# Sensor.net
KiCad netlist of a schematic drawn in EasyEDA
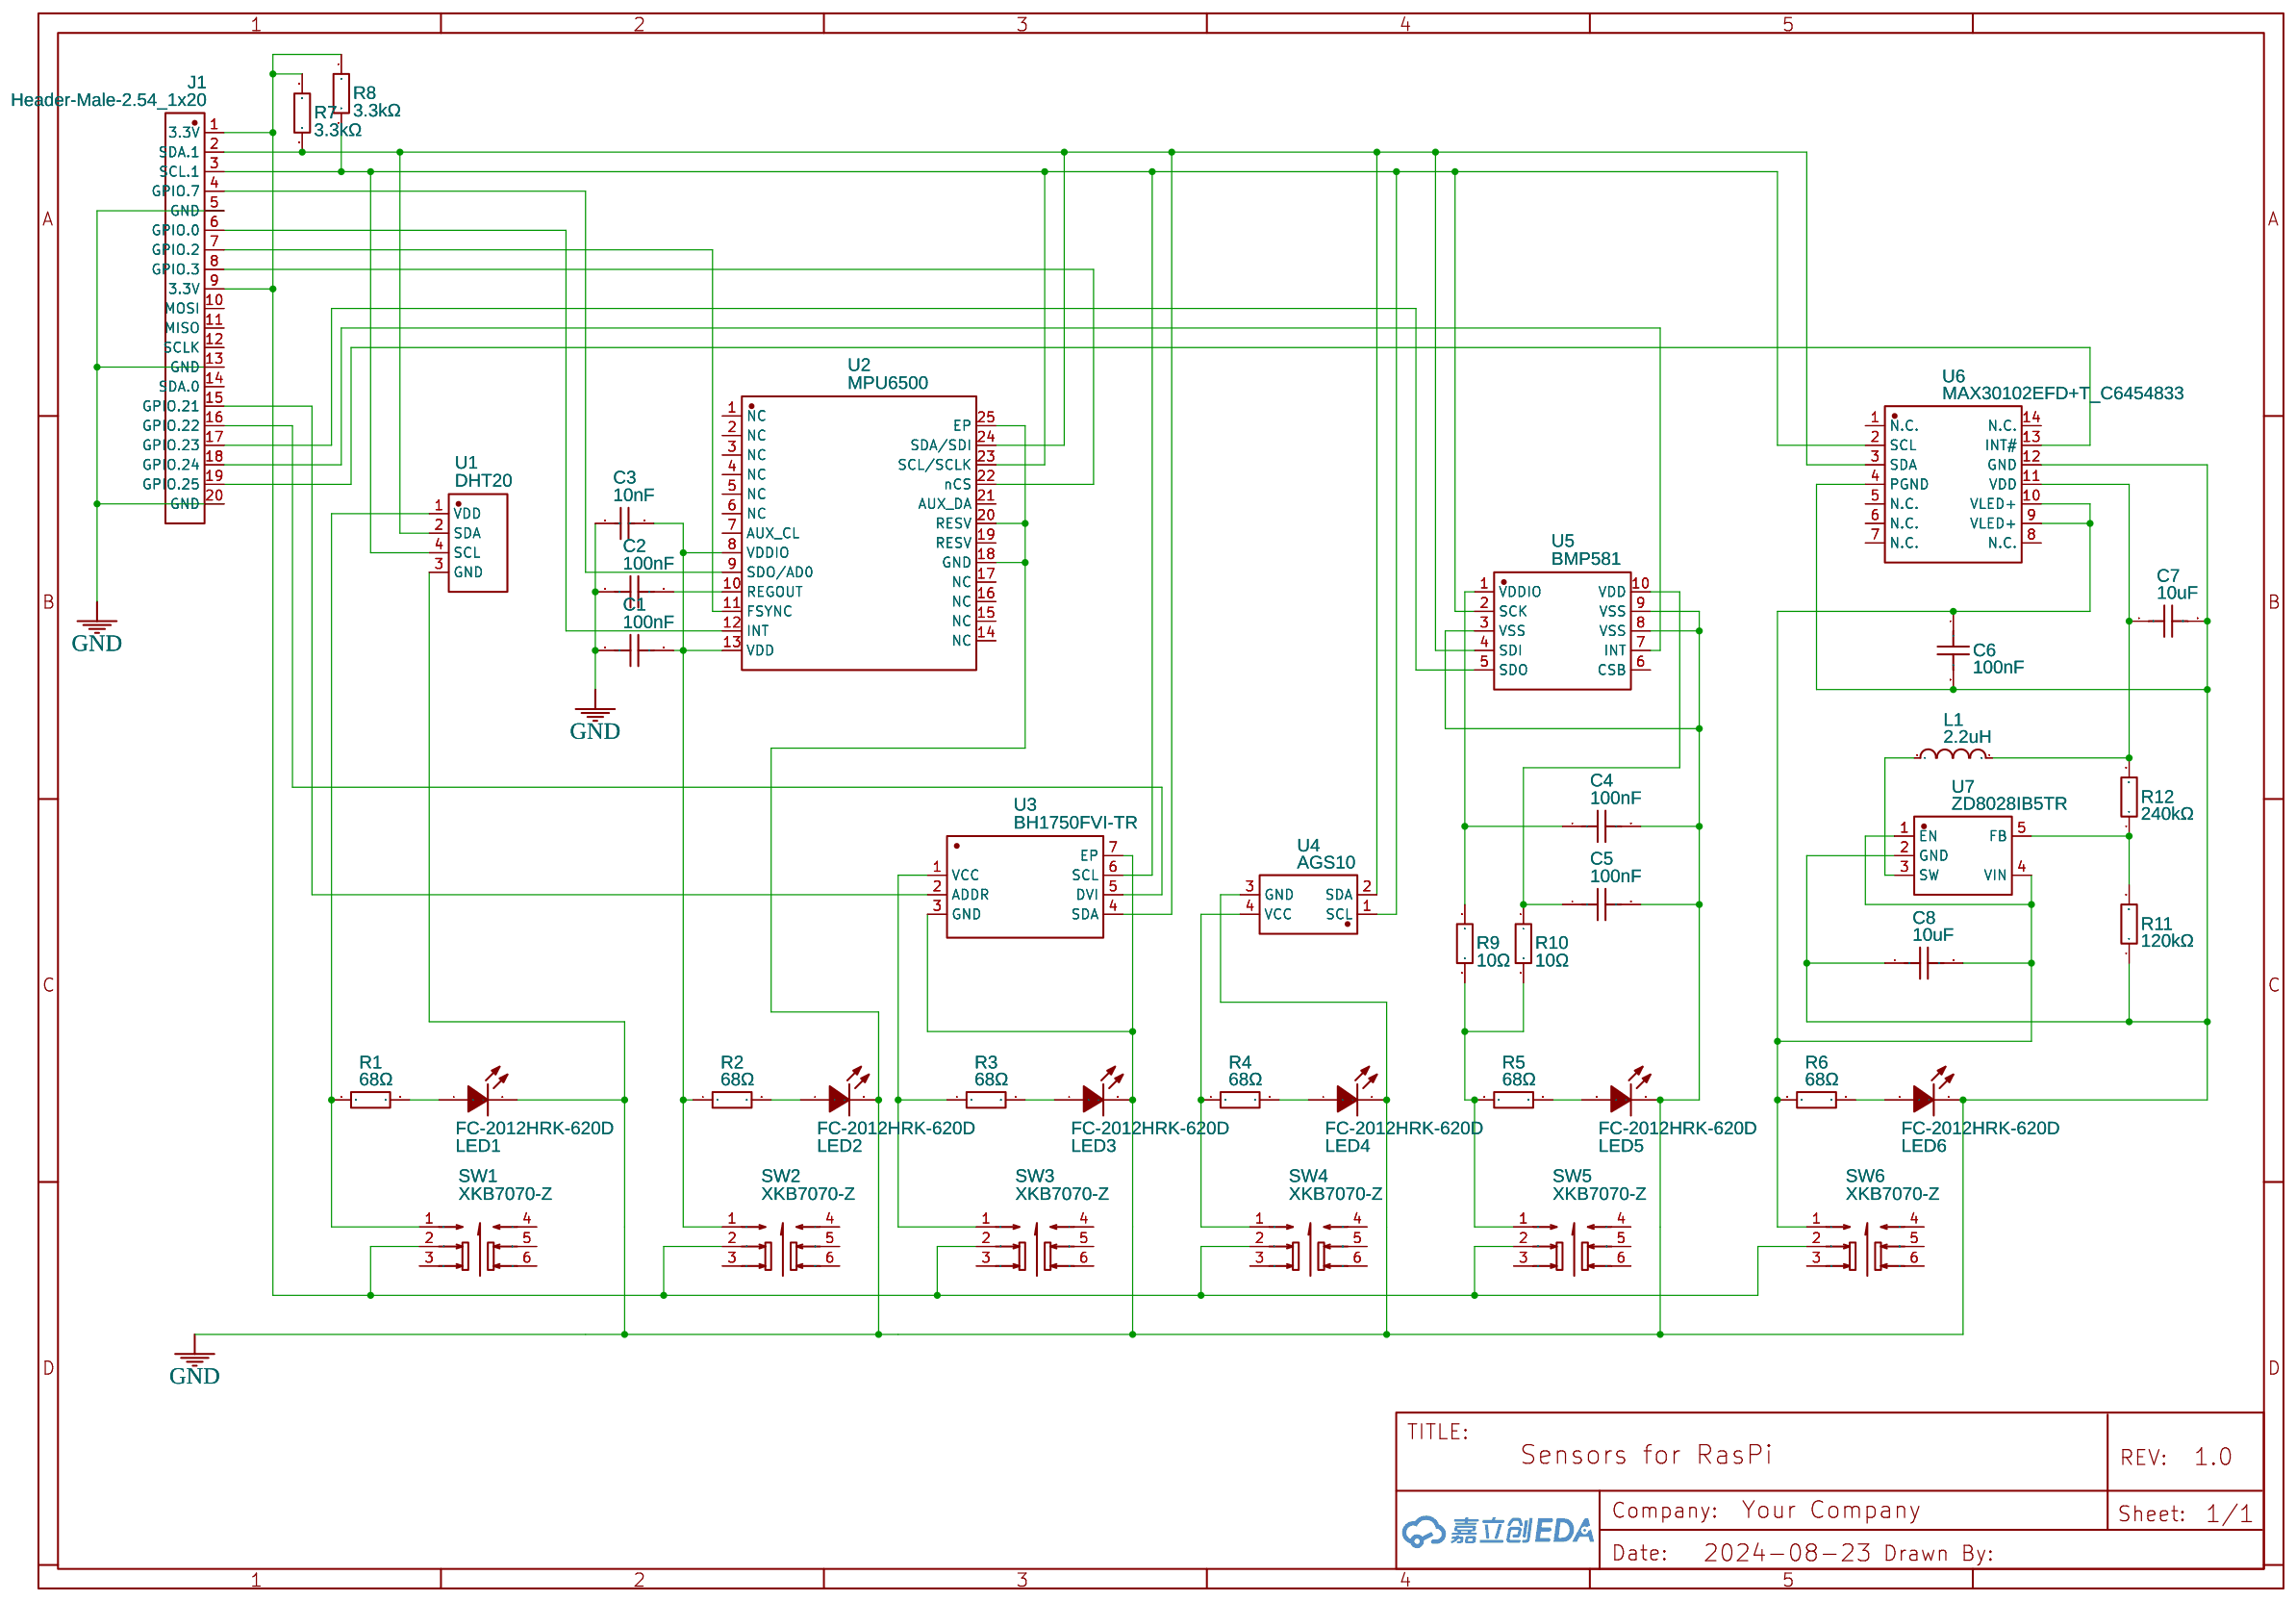
[diagram p0: schematic sheet]

(export (version "E")
  (design (tool "Eeschema 10.0.6"))
  (components
    (comp (ref "C1")
      (value "100nF")
      (fields
        (field (name "Manufacturer Part") "CC0603KRX7R9BB104")
        (field (name "Manufacturer") "YAGEO(国巨)")
      )
      (libsource (lib "") (part "CC0603KRX7R9BB104"))
    )
    (comp (ref "C2")
      (value "100nF")
      (fields
        (field (name "Manufacturer Part") "CC0603KRX7R9BB104")
        (field (name "Manufacturer") "YAGEO(国巨)")
      )
      (libsource (lib "") (part "CC0603KRX7R9BB104"))
    )
    (comp (ref "C3")
      (value "10nF")
      (fields
        (field (name "Manufacturer Part") "CC0603KRX7R9BB103")
        (field (name "Manufacturer") "YAGEO(国巨)")
      )
      (libsource (lib "") (part "CC0603KRX7R9BB103"))
    )
    (comp (ref "C4")
      (value "100nF")
      (fields
        (field (name "Manufacturer Part") "CC0603KRX7R9BB104")
        (field (name "Manufacturer") "YAGEO(国巨)")
      )
      (libsource (lib "") (part "CC0603KRX7R9BB104"))
    )
    (comp (ref "C5")
      (value "100nF")
      (fields
        (field (name "Manufacturer Part") "CC0603KRX7R9BB104")
        (field (name "Manufacturer") "YAGEO(国巨)")
      )
      (libsource (lib "") (part "CC0603KRX7R9BB104"))
    )
    (comp (ref "C6")
      (value "100nF")
      (fields
        (field (name "Manufacturer Part") "CC0603KRX7R9BB104")
        (field (name "Manufacturer") "YAGEO(国巨)")
      )
      (libsource (lib "") (part "CC0603KRX7R9BB104_1"))
    )
    (comp (ref "C7")
      (value "10uF")
      (fields
        (field (name "Manufacturer Part") "CL21A106KAYNNNE")
        (field (name "Manufacturer") "SAMSUNG(三星)")
      )
      (libsource (lib "") (part "CL21A106KAYNNNE"))
    )
    (comp (ref "C8")
      (value "10uF")
      (fields
        (field (name "Manufacturer Part") "CL21A106KAYNNNE")
        (field (name "Manufacturer") "SAMSUNG(三星)")
      )
      (libsource (lib "") (part "CL21A106KAYNNNE"))
    )
    (comp (ref "J1")
      (value "Header-Male-2.54_1x20")
      (fields (field (name "Manufacturer Part") "2.54-1*20P直针") (field (name "Manufacturer") "BOOMELE(博穆精密)"))
      (libsource (lib "") (part "Header-Male-2.54_1x20"))
    )
    (comp (ref "L1")
      (value "2.2uH")
      (fields (field (name "Manufacturer Part") "CMI201209U2R2KT") (field (name "Manufacturer") "FH(风华)"))
      (libsource (lib "") (part "CMI201209U2R2KT"))
    )
    (comp (ref "LED1")
      (value "FC-2012HRK-620D")
      (fields (field (name "Manufacturer Part") "NCD0805R1") (field (name "Manufacturer") "国星光电"))
      (libsource (lib "") (part "FC-2012HRK-620D"))
    )
    (comp (ref "LED2")
      (value "FC-2012HRK-620D")
      (fields (field (name "Manufacturer Part") "NCD0805R1") (field (name "Manufacturer") "国星光电"))
      (libsource (lib "") (part "FC-2012HRK-620D"))
    )
    (comp (ref "LED3")
      (value "FC-2012HRK-620D")
      (fields (field (name "Manufacturer Part") "NCD0805R1") (field (name "Manufacturer") "国星光电"))
      (libsource (lib "") (part "FC-2012HRK-620D"))
    )
    (comp (ref "LED4")
      (value "FC-2012HRK-620D")
      (fields (field (name "Manufacturer Part") "NCD0805R1") (field (name "Manufacturer") "国星光电"))
      (libsource (lib "") (part "FC-2012HRK-620D"))
    )
    (comp (ref "LED5")
      (value "FC-2012HRK-620D")
      (fields (field (name "Manufacturer Part") "NCD0805R1") (field (name "Manufacturer") "国星光电"))
      (libsource (lib "") (part "FC-2012HRK-620D"))
    )
    (comp (ref "LED6")
      (value "FC-2012HRK-620D")
      (fields (field (name "Manufacturer Part") "NCD0805R1") (field (name "Manufacturer") "国星光电"))
      (libsource (lib "") (part "FC-2012HRK-620D"))
    )
    (comp (ref "R1")
      (value "68Ω")
      (fields
        (field (name "Manufacturer Part") "0805W8F680JT5E")
        (field (name "Manufacturer") "UNI-ROYAL(厚声)")
      )
      (libsource (lib "") (part "0805W8F680JT5E"))
    )
    (comp (ref "R2")
      (value "68Ω")
      (fields
        (field (name "Manufacturer Part") "0805W8F680JT5E")
        (field (name "Manufacturer") "UNI-ROYAL(厚声)")
      )
      (libsource (lib "") (part "0805W8F680JT5E"))
    )
    (comp (ref "R3")
      (value "68Ω")
      (fields
        (field (name "Manufacturer Part") "0805W8F680JT5E")
        (field (name "Manufacturer") "UNI-ROYAL(厚声)")
      )
      (libsource (lib "") (part "0805W8F680JT5E"))
    )
    (comp (ref "R4")
      (value "68Ω")
      (fields
        (field (name "Manufacturer Part") "0805W8F680JT5E")
        (field (name "Manufacturer") "UNI-ROYAL(厚声)")
      )
      (libsource (lib "") (part "0805W8F680JT5E"))
    )
    (comp (ref "R5")
      (value "68Ω")
      (fields
        (field (name "Manufacturer Part") "0805W8F680JT5E")
        (field (name "Manufacturer") "UNI-ROYAL(厚声)")
      )
      (libsource (lib "") (part "0805W8F680JT5E"))
    )
    (comp (ref "R6")
      (value "68Ω")
      (fields
        (field (name "Manufacturer Part") "0805W8F680JT5E")
        (field (name "Manufacturer") "UNI-ROYAL(厚声)")
      )
      (libsource (lib "") (part "0805W8F680JT5E"))
    )
    (comp (ref "R7")
      (value "3.3kΩ")
      (fields
        (field (name "Manufacturer Part") "0603WAF3301T5E")
        (field (name "Manufacturer") "UNI-ROYAL(厚声)")
      )
      (libsource (lib "") (part "0603WAF3301T5E_1"))
    )
    (comp (ref "R8")
      (value "3.3kΩ")
      (fields
        (field (name "Manufacturer Part") "0603WAF3301T5E")
        (field (name "Manufacturer") "UNI-ROYAL(厚声)")
      )
      (libsource (lib "") (part "0603WAF3301T5E"))
    )
    (comp (ref "R9")
      (value "10Ω")
      (fields
        (field (name "Manufacturer Part") "0603WAF100JT5E")
        (field (name "Manufacturer") "UNI-ROYAL(厚声)")
      )
      (libsource (lib "") (part "0603WAF100JT5E_1"))
    )
    (comp (ref "R10")
      (value "10Ω")
      (fields
        (field (name "Manufacturer Part") "0603WAF100JT5E")
        (field (name "Manufacturer") "UNI-ROYAL(厚声)")
      )
      (libsource (lib "") (part "0603WAF100JT5E"))
    )
    (comp (ref "R11")
      (value "120kΩ")
      (fields
        (field (name "Manufacturer Part") "0603WAF1203T5E")
        (field (name "Manufacturer") "UNI-ROYAL(厚声)")
      )
      (libsource (lib "") (part "0603WAF1203T5E"))
    )
    (comp (ref "R12")
      (value "240kΩ")
      (fields
        (field (name "Manufacturer Part") "0603WAF2403T5E")
        (field (name "Manufacturer") "UNI-ROYAL(厚声)")
      )
      (libsource (lib "") (part "0603WAF2403T5E"))
    )
    (comp (ref "SW1")
      (value "XKB7070-Z")
      (fields (field (name "Manufacturer") "XKB Connectivity(中国星坤)"))
      (libsource (lib "") (part "XKB7070-Z"))
    )
    (comp (ref "SW2")
      (value "XKB7070-Z")
      (fields (field (name "Manufacturer") "XKB Connectivity(中国星坤)"))
      (libsource (lib "") (part "XKB7070-Z"))
    )
    (comp (ref "SW3")
      (value "XKB7070-Z")
      (fields (field (name "Manufacturer") "XKB Connectivity(中国星坤)"))
      (libsource (lib "") (part "XKB7070-Z"))
    )
    (comp (ref "SW4")
      (value "XKB7070-Z")
      (fields (field (name "Manufacturer") "XKB Connectivity(中国星坤)"))
      (libsource (lib "") (part "XKB7070-Z"))
    )
    (comp (ref "SW5")
      (value "XKB7070-Z")
      (fields (field (name "Manufacturer") "XKB Connectivity(中国星坤)"))
      (libsource (lib "") (part "XKB7070-Z"))
    )
    (comp (ref "SW6")
      (value "XKB7070-Z")
      (fields (field (name "Manufacturer") "XKB Connectivity(中国星坤)"))
      (libsource (lib "") (part "XKB7070-Z"))
    )
    (comp (ref "U1")
      (value "DHT20")
      (fields (field (name "Manufacturer") "广州奥松"))
      (libsource (lib "") (part "DHT20"))
    )
    (comp (ref "U2")
      (value "MPU6500")
      (fields
        (field (name "Manufacturer Part") "MPU-6500")
        (field (name "Manufacturer") "TDK InvenSense(应美盛)")
      )
      (libsource (lib "") (part "MPU6500"))
    )
    (comp (ref "U3")
      (value "BH1750FVI-TR")
      (fields (field (name "Manufacturer") "ROHM(罗姆)"))
      (libsource (lib "") (part "BH1750FVI-TR"))
    )
    (comp (ref "U4")
      (value "AGS10")
      (fields (field (name "Manufacturer") "广州奥松"))
      (libsource (lib "") (part "AGS10"))
    )
    (comp (ref "U5")
      (value "BMP581")
      (fields (field (name "Manufacturer") "Bosch(博世)"))
      (libsource (lib "") (part "BMP581"))
    )
    (comp (ref "U6")
      (value "MAX30102EFD+T_C6454833")
      (fields
        (field (name "Manufacturer Part") "MAX30102EFD+T")
        (field (name "Manufacturer") "ADI(亚德诺)/MAXIM(美信)")
      )
      (libsource (lib "") (part "MAX30102EFD+T_C6454833"))
    )
    (comp (ref "U7")
      (value "ZD8028IB5TR")
      (fields (field (name "Manufacturer") "Zetta(澜智)"))
      (libsource (lib "") (part "ZD8028IB5TR"))
    )
  )
  (nets
    (net (code "1") (name "GND") (class "Default")
      (node (ref "C1") (pin "1") (pinfunction "1_1") (pintype "unspecified"))
      (node (ref "C2") (pin "1") (pinfunction "1_1") (pintype "unspecified"))
      (node (ref "C3") (pin "1") (pinfunction "1_1") (pintype "input"))
      (node (ref "C4") (pin "2") (pinfunction "2_2") (pintype "unspecified"))
      (node (ref "C5") (pin "2") (pinfunction "2_2") (pintype "unspecified"))
      (node (ref "C6") (pin "2") (pinfunction "2_2") (pintype "unspecified"))
      (node (ref "C7") (pin "2") (pinfunction "2_2") (pintype "unspecified"))
      (node (ref "C8") (pin "1") (pinfunction "1_1") (pintype "unspecified"))
      (node (ref "J1") (pin "13") (pinfunction "GND_13") (pintype "unspecified"))
      (node (ref "J1") (pin "20") (pinfunction "GND_20") (pintype "unspecified"))
      (node (ref "J1") (pin "5") (pinfunction "GND_5") (pintype "unspecified"))
      (node (ref "LED1") (pin "2") (pinfunction "-_2") (pintype "unspecified"))
      (node (ref "LED2") (pin "2") (pinfunction "-_2") (pintype "unspecified"))
      (node (ref "LED3") (pin "2") (pinfunction "-_2") (pintype "unspecified"))
      (node (ref "LED4") (pin "2") (pinfunction "-_2") (pintype "unspecified"))
      (node (ref "LED5") (pin "2") (pinfunction "-_2") (pintype "unspecified"))
      (node (ref "LED6") (pin "2") (pinfunction "-_2") (pintype "unspecified"))
      (node (ref "R11") (pin "1") (pinfunction "1_1") (pintype "input"))
      (node (ref "U1") (pin "3") (pinfunction "GND_3") (pintype "unspecified"))
      (node (ref "U2") (pin "18") (pinfunction "GND_18") (pintype "unspecified"))
      (node (ref "U2") (pin "20") (pinfunction "RESV_20") (pintype "unspecified"))
      (node (ref "U2") (pin "25") (pinfunction "EP_25") (pintype "unspecified"))
      (node (ref "U3") (pin "3") (pinfunction "GND_3") (pintype "unspecified"))
      (node (ref "U3") (pin "7") (pinfunction "EP_7") (pintype "unspecified"))
      (node (ref "U4") (pin "3") (pinfunction "GND_3") (pintype "unspecified"))
      (node (ref "U5") (pin "3") (pinfunction "VSS_3") (pintype "unspecified"))
      (node (ref "U5") (pin "8") (pinfunction "VSS_8") (pintype "unspecified"))
      (node (ref "U5") (pin "9") (pinfunction "VSS_9") (pintype "unspecified"))
      (node (ref "U6") (pin "12") (pinfunction "GND_12") (pintype "unspecified"))
      (node (ref "U6") (pin "4") (pinfunction "PGND_4") (pintype "unspecified"))
      (node (ref "U7") (pin "2") (pinfunction "GND_2") (pintype "unspecified"))
    )
    (net (code "2") (name "Net-(J1-3.3V-Pad1)") (class "Default")
      (node (ref "J1") (pin "1") (pinfunction "3.3V_1") (pintype "unspecified"))
      (node (ref "J1") (pin "9") (pinfunction "3.3V_9") (pintype "unspecified"))
      (node (ref "R7") (pin "2") (pinfunction "2_2") (pintype "input"))
      (node (ref "R8") (pin "1") (pinfunction "1_1") (pintype "input"))
      (node (ref "SW1") (pin "2") (pinfunction "2_2") (pintype "unspecified"))
      (node (ref "SW2") (pin "2") (pinfunction "2_2") (pintype "unspecified"))
      (node (ref "SW3") (pin "2") (pinfunction "2_2") (pintype "unspecified"))
      (node (ref "SW4") (pin "2") (pinfunction "2_2") (pintype "unspecified"))
      (node (ref "SW5") (pin "2") (pinfunction "2_2") (pintype "unspecified"))
      (node (ref "SW6") (pin "2") (pinfunction "2_2") (pintype "unspecified"))
    )
    (net (code "3") (name "Net-(J1-GPIO.0)") (class "Default")
      (node (ref "J1") (pin "6") (pinfunction "GPIO.0_6") (pintype "unspecified"))
      (node (ref "U2") (pin "12") (pinfunction "INT_12") (pintype "unspecified"))
    )
    (net (code "4") (name "Net-(J1-GPIO.2)") (class "Default")
      (node (ref "J1") (pin "7") (pinfunction "GPIO.2_7") (pintype "unspecified"))
      (node (ref "U2") (pin "11") (pinfunction "FSYNC_11") (pintype "unspecified"))
    )
    (net (code "5") (name "Net-(J1-GPIO.3)") (class "Default")
      (node (ref "J1") (pin "8") (pinfunction "GPIO.3_8") (pintype "unspecified"))
      (node (ref "U2") (pin "22") (pinfunction "nCS_22") (pintype "unspecified"))
    )
    (net (code "6") (name "Net-(J1-GPIO.7)") (class "Default")
      (node (ref "J1") (pin "4") (pinfunction "GPIO.7_4") (pintype "unspecified"))
      (node (ref "U2") (pin "9") (pinfunction "SDO/AD0_9") (pintype "unspecified"))
    )
    (net (code "7") (name "Net-(J1-GPIO.21)") (class "Default")
      (node (ref "J1") (pin "15") (pinfunction "GPIO.21_15") (pintype "unspecified"))
      (node (ref "U3") (pin "2") (pinfunction "ADDR_2") (pintype "unspecified"))
    )
    (net (code "8") (name "Net-(J1-GPIO.22)") (class "Default")
      (node (ref "J1") (pin "16") (pinfunction "GPIO.22_16") (pintype "unspecified"))
      (node (ref "U3") (pin "5") (pinfunction "DVI_5") (pintype "unspecified"))
    )
    (net (code "9") (name "Net-(J1-GPIO.23)") (class "Default")
      (node (ref "J1") (pin "17") (pinfunction "GPIO.23_17") (pintype "unspecified"))
      (node (ref "U5") (pin "5") (pinfunction "SDO_5") (pintype "unspecified"))
    )
    (net (code "10") (name "Net-(J1-GPIO.24)") (class "Default")
      (node (ref "J1") (pin "18") (pinfunction "GPIO.24_18") (pintype "unspecified"))
      (node (ref "U5") (pin "7") (pinfunction "INT_7") (pintype "unspecified"))
    )
    (net (code "11") (name "Net-(J1-GPIO.25)") (class "Default")
      (node (ref "J1") (pin "19") (pinfunction "GPIO.25_19") (pintype "unspecified"))
      (node (ref "U6") (pin "13") (pinfunction "INT#_13") (pintype "unspecified"))
    )
    (net (code "12") (name "Net-(J1-SCL.1)") (class "Default")
      (node (ref "J1") (pin "3") (pinfunction "SCL.1_3") (pintype "unspecified"))
      (node (ref "R8") (pin "2") (pinfunction "2_2") (pintype "input"))
      (node (ref "U1") (pin "4") (pinfunction "SCL_4") (pintype "unspecified"))
      (node (ref "U2") (pin "23") (pinfunction "SCL/SCLK_23") (pintype "unspecified"))
      (node (ref "U3") (pin "6") (pinfunction "SCL_6") (pintype "unspecified"))
      (node (ref "U4") (pin "1") (pinfunction "SCL_1") (pintype "unspecified"))
      (node (ref "U5") (pin "2") (pinfunction "SCK_2") (pintype "unspecified"))
      (node (ref "U6") (pin "2") (pinfunction "SCL_2") (pintype "unspecified"))
    )
    (net (code "13") (name "Net-(J1-SDA.1)") (class "Default")
      (node (ref "J1") (pin "2") (pinfunction "SDA.1_2") (pintype "unspecified"))
      (node (ref "R7") (pin "1") (pinfunction "1_1") (pintype "input"))
      (node (ref "U1") (pin "2") (pinfunction "SDA_2") (pintype "unspecified"))
      (node (ref "U2") (pin "24") (pinfunction "SDA/SDI_24") (pintype "unspecified"))
      (node (ref "U3") (pin "4") (pinfunction "SDA_4") (pintype "unspecified"))
      (node (ref "U4") (pin "2") (pinfunction "SDA_2") (pintype "unspecified"))
      (node (ref "U5") (pin "4") (pinfunction "SDI_4") (pintype "unspecified"))
      (node (ref "U6") (pin "3") (pinfunction "SDA_3") (pintype "unspecified"))
    )
    (net (code "14") (name "Net-(LED1-+)") (class "Default")
      (node (ref "LED1") (pin "1") (pinfunction "+_1") (pintype "unspecified"))
      (node (ref "R1") (pin "2") (pinfunction "2_2") (pintype "input"))
    )
    (net (code "15") (name "Net-(LED2-+)") (class "Default")
      (node (ref "LED2") (pin "1") (pinfunction "+_1") (pintype "unspecified"))
      (node (ref "R2") (pin "2") (pinfunction "2_2") (pintype "input"))
    )
    (net (code "16") (name "Net-(LED3-+)") (class "Default")
      (node (ref "LED3") (pin "1") (pinfunction "+_1") (pintype "unspecified"))
      (node (ref "R3") (pin "2") (pinfunction "2_2") (pintype "input"))
    )
    (net (code "17") (name "Net-(LED4-+)") (class "Default")
      (node (ref "LED4") (pin "1") (pinfunction "+_1") (pintype "unspecified"))
      (node (ref "R4") (pin "2") (pinfunction "2_2") (pintype "input"))
    )
    (net (code "18") (name "Net-(LED5-+)") (class "Default")
      (node (ref "LED5") (pin "1") (pinfunction "+_1") (pintype "unspecified"))
      (node (ref "R5") (pin "2") (pinfunction "2_2") (pintype "input"))
    )
    (net (code "19") (name "Net-(LED6-+)") (class "Default")
      (node (ref "LED6") (pin "1") (pinfunction "+_1") (pintype "unspecified"))
      (node (ref "R6") (pin "2") (pinfunction "2_2") (pintype "input"))
    )
    (net (code "20") (name "Net-(R10-Pad2)") (class "Default")
      (node (ref "R10") (pin "2") (pinfunction "2_2") (pintype "input"))
      (node (ref "R5") (pin "1") (pinfunction "1_1") (pintype "input"))
      (node (ref "R9") (pin "1") (pinfunction "1_1") (pintype "input"))
      (node (ref "SW5") (pin "1") (pinfunction "1_1") (pintype "unspecified"))
    )
    (net (code "21") (name "Net-(U1-VDD)") (class "Default")
      (node (ref "R1") (pin "1") (pinfunction "1_1") (pintype "input"))
      (node (ref "SW1") (pin "1") (pinfunction "1_1") (pintype "unspecified"))
      (node (ref "U1") (pin "1") (pinfunction "VDD_1") (pintype "unspecified"))
    )
    (net (code "22") (name "Net-(U2-REGOUT)") (class "Default")
      (node (ref "C2") (pin "2") (pinfunction "2_2") (pintype "unspecified"))
      (node (ref "U2") (pin "10") (pinfunction "REGOUT_10") (pintype "unspecified"))
    )
    (net (code "23") (name "Net-(U2-VDD)") (class "Default")
      (node (ref "C1") (pin "2") (pinfunction "2_2") (pintype "unspecified"))
      (node (ref "C3") (pin "2") (pinfunction "2_2") (pintype "input"))
      (node (ref "R2") (pin "1") (pinfunction "1_1") (pintype "input"))
      (node (ref "SW2") (pin "1") (pinfunction "1_1") (pintype "unspecified"))
      (node (ref "U2") (pin "13") (pinfunction "VDD_13") (pintype "unspecified"))
      (node (ref "U2") (pin "8") (pinfunction "VDDIO_8") (pintype "unspecified"))
    )
    (net (code "24") (name "Net-(U3-VCC)") (class "Default")
      (node (ref "R3") (pin "1") (pinfunction "1_1") (pintype "input"))
      (node (ref "SW3") (pin "1") (pinfunction "1_1") (pintype "unspecified"))
      (node (ref "U3") (pin "1") (pinfunction "VCC_1") (pintype "unspecified"))
    )
    (net (code "25") (name "Net-(U4-VCC)") (class "Default")
      (node (ref "R4") (pin "1") (pinfunction "1_1") (pintype "input"))
      (node (ref "SW4") (pin "1") (pinfunction "1_1") (pintype "unspecified"))
      (node (ref "U4") (pin "4") (pinfunction "VCC_4") (pintype "unspecified"))
    )
    (net (code "26") (name "Net-(U5-VDD)") (class "Default")
      (node (ref "C5") (pin "1") (pinfunction "1_1") (pintype "unspecified"))
      (node (ref "R10") (pin "1") (pinfunction "1_1") (pintype "input"))
      (node (ref "U5") (pin "10") (pinfunction "VDD_10") (pintype "unspecified"))
    )
    (net (code "27") (name "Net-(U5-VDDIO)") (class "Default")
      (node (ref "C4") (pin "1") (pinfunction "1_1") (pintype "unspecified"))
      (node (ref "R9") (pin "2") (pinfunction "2_2") (pintype "input"))
      (node (ref "U5") (pin "1") (pinfunction "VDDIO_1") (pintype "unspecified"))
    )
    (net (code "28") (name "Net-(U6-VDD)") (class "Default")
      (node (ref "C7") (pin "1") (pinfunction "1_1") (pintype "unspecified"))
      (node (ref "L1") (pin "2") (pinfunction "2_2") (pintype "unspecified"))
      (node (ref "R12") (pin "2") (pinfunction "2_2") (pintype "input"))
      (node (ref "U6") (pin "11") (pinfunction "VDD_11") (pintype "unspecified"))
    )
    (net (code "29") (name "Net-(U7-EN)") (class "Default")
      (node (ref "C6") (pin "1") (pinfunction "1_1") (pintype "unspecified"))
      (node (ref "C8") (pin "2") (pinfunction "2_2") (pintype "unspecified"))
      (node (ref "R6") (pin "1") (pinfunction "1_1") (pintype "input"))
      (node (ref "SW6") (pin "1") (pinfunction "1_1") (pintype "unspecified"))
      (node (ref "U6") (pin "10") (pinfunction "VLED+_10") (pintype "unspecified"))
      (node (ref "U6") (pin "9") (pinfunction "VLED+_9") (pintype "unspecified"))
      (node (ref "U7") (pin "1") (pinfunction "EN_1") (pintype "unspecified"))
      (node (ref "U7") (pin "4") (pinfunction "VIN_4") (pintype "unspecified"))
    )
    (net (code "30") (name "Net-(U7-FB)") (class "Default")
      (node (ref "R11") (pin "2") (pinfunction "2_2") (pintype "input"))
      (node (ref "R12") (pin "1") (pinfunction "1_1") (pintype "input"))
      (node (ref "U7") (pin "5") (pinfunction "FB_5") (pintype "unspecified"))
    )
    (net (code "31") (name "Net-(U7-SW)") (class "Default")
      (node (ref "L1") (pin "1") (pinfunction "1_1") (pintype "unspecified"))
      (node (ref "U7") (pin "3") (pinfunction "SW_3") (pintype "unspecified"))
    )
    (net (code "32") (name "unconnected-(J1-MISO-Pad11)") (class "Default")
      (node (ref "J1") (pin "11") (pinfunction "MISO_11") (pintype "unspecified"))
    )
    (net (code "33") (name "unconnected-(J1-MOSI-Pad10)") (class "Default")
      (node (ref "J1") (pin "10") (pinfunction "MOSI_10") (pintype "unspecified"))
    )
    (net (code "34") (name "unconnected-(J1-SCLK-Pad12)") (class "Default")
      (node (ref "J1") (pin "12") (pinfunction "SCLK_12") (pintype "unspecified"))
    )
    (net (code "35") (name "unconnected-(J1-SDA.0-Pad14)") (class "Default")
      (node (ref "J1") (pin "14") (pinfunction "SDA.0_14") (pintype "unspecified"))
    )
    (net (code "36") (name "unconnected-(SW1-Pad3)") (class "Default")
      (node (ref "SW1") (pin "3") (pinfunction "3_3") (pintype "unspecified"))
    )
    (net (code "37") (name "unconnected-(SW1-Pad4)") (class "Default")
      (node (ref "SW1") (pin "4") (pinfunction "4_4") (pintype "unspecified"))
    )
    (net (code "38") (name "unconnected-(SW1-Pad5)") (class "Default")
      (node (ref "SW1") (pin "5") (pinfunction "5_5") (pintype "unspecified"))
    )
    (net (code "39") (name "unconnected-(SW1-Pad6)") (class "Default")
      (node (ref "SW1") (pin "6") (pinfunction "6_6") (pintype "unspecified"))
    )
    (net (code "40") (name "unconnected-(SW2-Pad3)") (class "Default")
      (node (ref "SW2") (pin "3") (pinfunction "3_3") (pintype "unspecified"))
    )
    (net (code "41") (name "unconnected-(SW2-Pad4)") (class "Default")
      (node (ref "SW2") (pin "4") (pinfunction "4_4") (pintype "unspecified"))
    )
    (net (code "42") (name "unconnected-(SW2-Pad5)") (class "Default")
      (node (ref "SW2") (pin "5") (pinfunction "5_5") (pintype "unspecified"))
    )
    (net (code "43") (name "unconnected-(SW2-Pad6)") (class "Default")
      (node (ref "SW2") (pin "6") (pinfunction "6_6") (pintype "unspecified"))
    )
    (net (code "44") (name "unconnected-(SW3-Pad3)") (class "Default")
      (node (ref "SW3") (pin "3") (pinfunction "3_3") (pintype "unspecified"))
    )
    (net (code "45") (name "unconnected-(SW3-Pad4)") (class "Default")
      (node (ref "SW3") (pin "4") (pinfunction "4_4") (pintype "unspecified"))
    )
    (net (code "46") (name "unconnected-(SW3-Pad5)") (class "Default")
      (node (ref "SW3") (pin "5") (pinfunction "5_5") (pintype "unspecified"))
    )
    (net (code "47") (name "unconnected-(SW3-Pad6)") (class "Default")
      (node (ref "SW3") (pin "6") (pinfunction "6_6") (pintype "unspecified"))
    )
    (net (code "48") (name "unconnected-(SW4-Pad3)") (class "Default")
      (node (ref "SW4") (pin "3") (pinfunction "3_3") (pintype "unspecified"))
    )
    (net (code "49") (name "unconnected-(SW4-Pad4)") (class "Default")
      (node (ref "SW4") (pin "4") (pinfunction "4_4") (pintype "unspecified"))
    )
    (net (code "50") (name "unconnected-(SW4-Pad5)") (class "Default")
      (node (ref "SW4") (pin "5") (pinfunction "5_5") (pintype "unspecified"))
    )
    (net (code "51") (name "unconnected-(SW4-Pad6)") (class "Default")
      (node (ref "SW4") (pin "6") (pinfunction "6_6") (pintype "unspecified"))
    )
    (net (code "52") (name "unconnected-(SW5-Pad3)") (class "Default")
      (node (ref "SW5") (pin "3") (pinfunction "3_3") (pintype "unspecified"))
    )
    (net (code "53") (name "unconnected-(SW5-Pad4)") (class "Default")
      (node (ref "SW5") (pin "4") (pinfunction "4_4") (pintype "unspecified"))
    )
    (net (code "54") (name "unconnected-(SW5-Pad5)") (class "Default")
      (node (ref "SW5") (pin "5") (pinfunction "5_5") (pintype "unspecified"))
    )
    (net (code "55") (name "unconnected-(SW5-Pad6)") (class "Default")
      (node (ref "SW5") (pin "6") (pinfunction "6_6") (pintype "unspecified"))
    )
    (net (code "56") (name "unconnected-(SW6-Pad3)") (class "Default")
      (node (ref "SW6") (pin "3") (pinfunction "3_3") (pintype "unspecified"))
    )
    (net (code "57") (name "unconnected-(SW6-Pad4)") (class "Default")
      (node (ref "SW6") (pin "4") (pinfunction "4_4") (pintype "unspecified"))
    )
    (net (code "58") (name "unconnected-(SW6-Pad5)") (class "Default")
      (node (ref "SW6") (pin "5") (pinfunction "5_5") (pintype "unspecified"))
    )
    (net (code "59") (name "unconnected-(SW6-Pad6)") (class "Default")
      (node (ref "SW6") (pin "6") (pinfunction "6_6") (pintype "unspecified"))
    )
    (net (code "60") (name "unconnected-(U2-AUX_CL-Pad7)") (class "Default")
      (node (ref "U2") (pin "7") (pinfunction "AUX_CL_7") (pintype "unspecified"))
    )
    (net (code "61") (name "unconnected-(U2-AUX_DA-Pad21)") (class "Default")
      (node (ref "U2") (pin "21") (pinfunction "AUX_DA_21") (pintype "unspecified"))
    )
    (net (code "62") (name "unconnected-(U2-NC-Pad1)") (class "Default")
      (node (ref "U2") (pin "1") (pinfunction "NC_1") (pintype "unspecified"))
    )
    (net (code "63") (name "unconnected-(U2-NC-Pad2)") (class "Default")
      (node (ref "U2") (pin "2") (pinfunction "NC_2") (pintype "unspecified"))
    )
    (net (code "64") (name "unconnected-(U2-NC-Pad3)") (class "Default")
      (node (ref "U2") (pin "3") (pinfunction "NC_3") (pintype "unspecified"))
    )
    (net (code "65") (name "unconnected-(U2-NC-Pad4)") (class "Default")
      (node (ref "U2") (pin "4") (pinfunction "NC_4") (pintype "unspecified"))
    )
    (net (code "66") (name "unconnected-(U2-NC-Pad5)") (class "Default")
      (node (ref "U2") (pin "5") (pinfunction "NC_5") (pintype "unspecified"))
    )
    (net (code "67") (name "unconnected-(U2-NC-Pad6)") (class "Default")
      (node (ref "U2") (pin "6") (pinfunction "NC_6") (pintype "unspecified"))
    )
    (net (code "68") (name "unconnected-(U2-NC-Pad14)") (class "Default")
      (node (ref "U2") (pin "14") (pinfunction "NC_14") (pintype "unspecified"))
    )
    (net (code "69") (name "unconnected-(U2-NC-Pad15)") (class "Default")
      (node (ref "U2") (pin "15") (pinfunction "NC_15") (pintype "unspecified"))
    )
    (net (code "70") (name "unconnected-(U2-NC-Pad16)") (class "Default")
      (node (ref "U2") (pin "16") (pinfunction "NC_16") (pintype "unspecified"))
    )
    (net (code "71") (name "unconnected-(U2-NC-Pad17)") (class "Default")
      (node (ref "U2") (pin "17") (pinfunction "NC_17") (pintype "unspecified"))
    )
    (net (code "72") (name "unconnected-(U2-RESV-Pad19)") (class "Default")
      (node (ref "U2") (pin "19") (pinfunction "RESV_19") (pintype "unspecified"))
    )
    (net (code "73") (name "unconnected-(U5-CSB-Pad6)") (class "Default")
      (node (ref "U5") (pin "6") (pinfunction "CSB_6") (pintype "unspecified"))
    )
    (net (code "74") (name "unconnected-(U6-N.C.-Pad1)") (class "Default")
      (node (ref "U6") (pin "1") (pinfunction "N.C._1") (pintype "unspecified"))
    )
    (net (code "75") (name "unconnected-(U6-N.C.-Pad5)") (class "Default")
      (node (ref "U6") (pin "5") (pinfunction "N.C._5") (pintype "unspecified"))
    )
    (net (code "76") (name "unconnected-(U6-N.C.-Pad6)") (class "Default")
      (node (ref "U6") (pin "6") (pinfunction "N.C._6") (pintype "unspecified"))
    )
    (net (code "77") (name "unconnected-(U6-N.C.-Pad7)") (class "Default")
      (node (ref "U6") (pin "7") (pinfunction "N.C._7") (pintype "unspecified"))
    )
    (net (code "78") (name "unconnected-(U6-N.C.-Pad8)") (class "Default")
      (node (ref "U6") (pin "8") (pinfunction "N.C._8") (pintype "unspecified"))
    )
    (net (code "79") (name "unconnected-(U6-N.C.-Pad14)") (class "Default")
      (node (ref "U6") (pin "14") (pinfunction "N.C._14") (pintype "unspecified"))
    )
  )
)
